# WIFI.net
KiCad netlist of a schematic drawn in Altium Designer
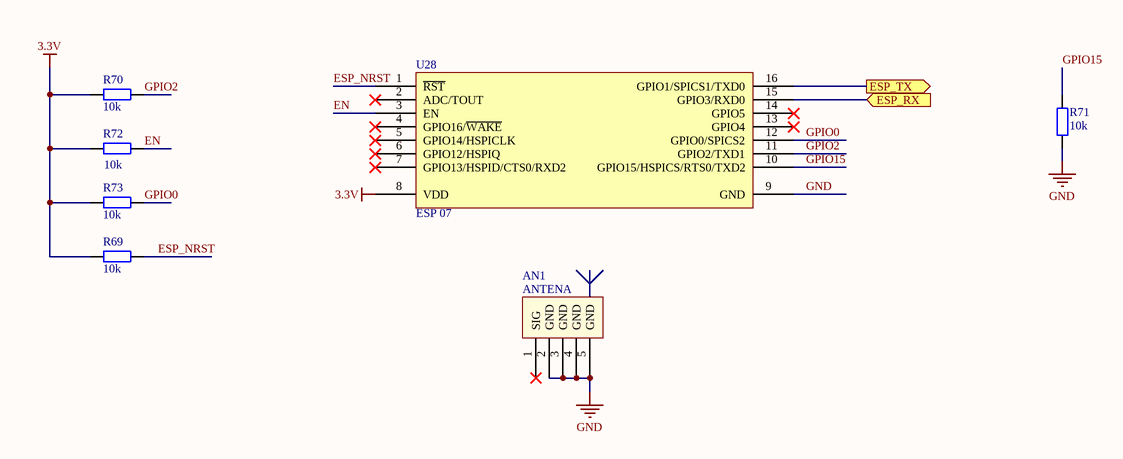
[diagram p0: WIFI.SchDoc]

(export (version "E")
  (design (tool "Eeschema 10.0.6"))
  (components
    (comp (ref "AN1")
      (value "ANTENA")
      (footprint "DE ANTEN SMA CONG")
      (description "Generic Antenna")
      (libsource (lib "Altium_Lib_by_KhueNguyenCreator") (part "ANTEN SMA CONG"))
    )
    (comp (ref "R69")
      (value "10k")
      (footprint "tro smd 0805")
      (description "Dán")
      (libsource (lib "Altium_Lib_by_KhueNguyenCreator") (part "Tro 0805 1% 10k"))
    )
    (comp (ref "R70")
      (value "10k")
      (footprint "tro smd 0805")
      (description "Dán")
      (libsource (lib "Altium_Lib_by_KhueNguyenCreator") (part "Tro 0805 1% 10k"))
    )
    (comp (ref "R71")
      (value "10k")
      (footprint "tro smd 0805")
      (description "Dán")
      (libsource (lib "Altium_Lib_by_KhueNguyenCreator") (part "Tro 0805 1% 10k"))
    )
    (comp (ref "R72")
      (value "10k")
      (footprint "tro smd 0805")
      (description "Dán")
      (libsource (lib "Altium_Lib_by_KhueNguyenCreator") (part "Tro 0805 1% 10k"))
    )
    (comp (ref "R73")
      (value "10k")
      (footprint "tro smd 0805")
      (description "Dán")
      (libsource (lib "Altium_Lib_by_KhueNguyenCreator") (part "Tro 0805 1% 10k"))
    )
    (comp (ref "U28")
      (value "ESP 07")
      (footprint "ESP8266 07")
      (description "ESP8266 07 16 Pin")
      (libsource (lib "Altium_Lib_by_KhueNguyenCreator") (part "ESP8266 07"))
    )
  )
  (nets
    (net (code "1") (name "/EN") (class "Default")
      (node (ref "R72") (pin "1") (pinfunction "1_1") (pintype "passive"))
      (node (ref "U28") (pin "3") (pinfunction "EN_3") (pintype "passive"))
    )
    (net (code "2") (name "/ESP_NRST") (class "Default")
      (node (ref "R69") (pin "2") (pinfunction "2_2") (pintype "passive"))
      (node (ref "U28") (pin "1") (pinfunction "~{RST}_1") (pintype "passive"))
    )
    (net (code "3") (name "/ESP_RX") (class "Default")
      (node (ref "U28") (pin "15") (pinfunction "GPIO3/RXD0_15") (pintype "passive"))
    )
    (net (code "4") (name "/ESP_TX") (class "Default")
      (node (ref "U28") (pin "16") (pinfunction "GPIO1/SPICS1/TXD0_16") (pintype "passive"))
    )
    (net (code "5") (name "/GPIO0") (class "Default")
      (node (ref "R73") (pin "1") (pinfunction "1_1") (pintype "passive"))
      (node (ref "U28") (pin "12") (pinfunction "GPIO0/SPICS2_12") (pintype "passive"))
    )
    (net (code "6") (name "/GPIO2") (class "Default")
      (node (ref "R70") (pin "1") (pinfunction "1_1") (pintype "passive"))
      (node (ref "U28") (pin "11") (pinfunction "GPIO2/TXD1_11") (pintype "passive"))
    )
    (net (code "7") (name "/GPIO15") (class "Default")
      (node (ref "R71") (pin "2") (pinfunction "2_2") (pintype "passive"))
      (node (ref "U28") (pin "10") (pinfunction "GPIO15/HSPICS/RTS0/TXD2_10") (pintype "passive"))
    )
    (net (code "8") (name "3.3V") (class "Default")
      (node (ref "R69") (pin "1") (pinfunction "1_1") (pintype "passive"))
      (node (ref "R70") (pin "2") (pinfunction "2_2") (pintype "passive"))
      (node (ref "R72") (pin "2") (pinfunction "2_2") (pintype "passive"))
      (node (ref "R73") (pin "2") (pinfunction "2_2") (pintype "passive"))
      (node (ref "U28") (pin "8") (pinfunction "VDD_8") (pintype "passive"))
    )
    (net (code "9") (name "GND") (class "Default")
      (node (ref "AN1") (pin "2") (pinfunction "GND_2") (pintype "passive"))
      (node (ref "AN1") (pin "3") (pinfunction "GND_3") (pintype "passive"))
      (node (ref "AN1") (pin "4") (pinfunction "GND_4") (pintype "passive"))
      (node (ref "AN1") (pin "5") (pinfunction "GND_5") (pintype "passive"))
      (node (ref "R71") (pin "1") (pinfunction "1_1") (pintype "passive"))
      (node (ref "U28") (pin "9") (pinfunction "GND_9") (pintype "passive"))
    )
    (net (code "10") (name "unconnected-(AN1-SIG-Pad1)") (class "Default")
      (node (ref "AN1") (pin "1") (pinfunction "SIG_1") (pintype "passive+no_connect"))
    )
    (net (code "11") (name "unconnected-(U28-ADC{slash}TOUT-Pad2)") (class "Default")
      (node (ref "U28") (pin "2") (pinfunction "ADC/TOUT_2") (pintype "passive+no_connect"))
    )
    (net (code "12") (name "unconnected-(U28-GPIO4-Pad13)") (class "Default")
      (node (ref "U28") (pin "13") (pinfunction "GPIO4_13") (pintype "passive+no_connect"))
    )
    (net (code "13") (name "unconnected-(U28-GPIO5-Pad14)") (class "Default")
      (node (ref "U28") (pin "14") (pinfunction "GPIO5_14") (pintype "passive+no_connect"))
    )
    (net (code "14") (name "unconnected-(U28-GPIO12{slash}HSPIQ-Pad6)") (class "Default")
      (node (ref "U28") (pin "6") (pinfunction "GPIO12/HSPIQ_6") (pintype "passive+no_connect"))
    )
    (net (code "15") (name "unconnected-(U28-GPIO13{slash}HSPID{slash}CTS0{slash}RXD2-Pad7)") (class "Default")
      (node (ref "U28") (pin "7") (pinfunction "GPIO13/HSPID/CTS0/RXD2_7") (pintype "passive+no_connect"))
    )
    (net (code "16") (name "unconnected-(U28-GPIO14{slash}HSPICLK-Pad5)") (class "Default")
      (node (ref "U28") (pin "5") (pinfunction "GPIO14/HSPICLK_5") (pintype "passive+no_connect"))
    )
    (net (code "17") (name "unconnected-(U28-GPIO16{slash}~{WAKE}-Pad4)") (class "Default")
      (node (ref "U28") (pin "4") (pinfunction "GPIO16/~{WAKE}_4") (pintype "passive+no_connect"))
    )
  )
)
